# Sheet4_misc.net
KiCad netlist of a schematic drawn in Altium Designer
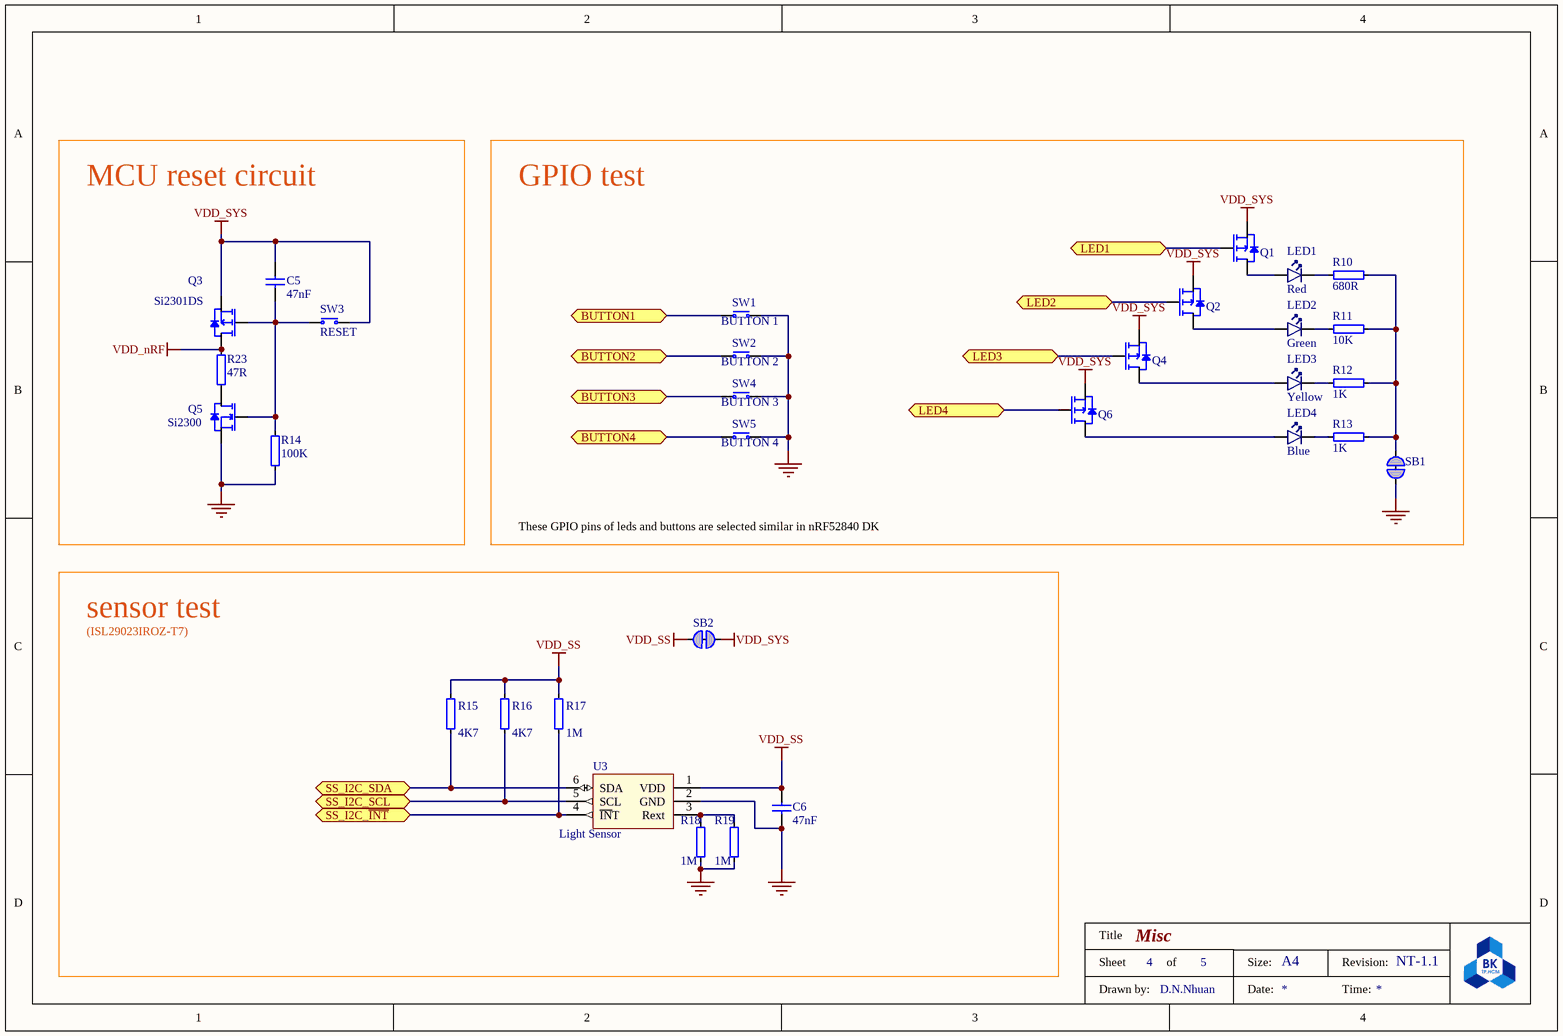
[diagram p0: Sheet4_misc.SchDoc]

(export (version "E")
  (design (tool "Eeschema 10.0.6"))
  (components
    (comp (ref "C5")
      (value "47nF")
      (footprint "0402 imperial")
      (description "Genaral Schematic")
      (fields (field (name "TOLERANCE") "±5%"))
      (libsource (lib "Project_Library") (part "Capacitor"))
    )
    (comp (ref "C6")
      (value "47nF")
      (footprint "0402 imperial")
      (description "Genaral Schematic")
      (fields (field (name "TOLERANCE") "±5%"))
      (libsource (lib "Project_Library") (part "Capacitor"))
    )
    (comp (ref "LED1")
      (value "Red")
      (footprint "LED_0603")
      (description "General Schematic")
      (libsource (lib "Project_library") (part "LED"))
    )
    (comp (ref "LED2")
      (value "Green")
      (footprint "LED_0603")
      (description "General Schematic")
      (libsource (lib "Project_library") (part "LED"))
    )
    (comp (ref "LED3")
      (value "Yellow")
      (footprint "LED_0603")
      (description "General Schematic")
      (libsource (lib "Project_library") (part "LED"))
    )
    (comp (ref "LED4")
      (value "Blue")
      (footprint "LED_0603")
      (description "General Schematic")
      (libsource (lib "Project_library") (part "LED"))
    )
    (comp (ref "Q1")
      (value "Si2301DS")
      (footprint "SOT-23")
      (description "SOT-23 1-G 2-S 3-D")
      (libsource (lib "Project_library") (part "MOS-P"))
    )
    (comp (ref "Q2")
      (value "Si2301DS")
      (footprint "SOT-23")
      (description "SOT-23 1-G 2-S 3-D")
      (libsource (lib "Project_library") (part "MOS-P"))
    )
    (comp (ref "Q3")
      (value "Si2301DS")
      (footprint "SOT-23")
      (description "SOT-23 1-G 2-S 3-D")
      (libsource (lib "Project_Library") (part "MOS-P"))
    )
    (comp (ref "Q4")
      (value "Si2301DS")
      (footprint "SOT-23")
      (description "SOT-23 1-G 2-S 3-D")
      (libsource (lib "Project_library") (part "MOS-P"))
    )
    (comp (ref "Q5")
      (value "Si2300")
      (footprint "SOT-23")
      (description "SOT-23 1-G 2-S 3-D")
      (libsource (lib "Project_Library") (part "MOS-N"))
    )
    (comp (ref "Q6")
      (value "Si2301DS")
      (footprint "SOT-23")
      (description "SOT-23 1-G 2-S 3-D")
      (libsource (lib "Project_library") (part "MOS-P"))
    )
    (comp (ref "R10")
      (value "680R")
      (footprint "0805_Imperial")
      (description "General Schematic")
      (fields (field (name "TOLERANCE") "±5%"))
      (libsource (lib "Project_library") (part "Resistor"))
    )
    (comp (ref "R11")
      (value "10K")
      (footprint "0805_Imperial")
      (description "General Schematic")
      (fields (field (name "TOLERANCE") "±5%"))
      (libsource (lib "Project_library") (part "Resistor"))
    )
    (comp (ref "R12")
      (value "1K")
      (footprint "0805_Imperial")
      (description "General Schematic")
      (fields (field (name "TOLERANCE") "±5%"))
      (libsource (lib "Project_library") (part "Resistor"))
    )
    (comp (ref "R13")
      (value "1K")
      (footprint "0805_Imperial")
      (description "General Schematic")
      (fields (field (name "TOLERANCE") "±5%"))
      (libsource (lib "Project_library") (part "Resistor"))
    )
    (comp (ref "R14")
      (value "100K")
      (footprint "0402 imperial")
      (description "General Schematic")
      (fields (field (name "TOLERANCE") "±5%"))
      (libsource (lib "Project_Library") (part "Resistor"))
    )
    (comp (ref "R15")
      (value "4K7")
      (footprint "0402 imperial")
      (description "General Schematic")
      (fields (field (name "TOLERANCE") "±5%"))
      (libsource (lib "Project_Library") (part "Resistor"))
    )
    (comp (ref "R16")
      (value "4K7")
      (footprint "0402 imperial")
      (description "General Schematic")
      (fields (field (name "TOLERANCE") "±5%"))
      (libsource (lib "Project_Library") (part "Resistor"))
    )
    (comp (ref "R17")
      (value "1M")
      (footprint "0402 imperial")
      (description "General Schematic")
      (fields (field (name "TOLERANCE") "±5%"))
      (libsource (lib "Project_Library") (part "Resistor"))
    )
    (comp (ref "R18")
      (value "1M")
      (footprint "0402 imperial")
      (description "General Schematic")
      (fields (field (name "TOLERANCE") "±1%"))
      (libsource (lib "Project_Library") (part "Resistor"))
    )
    (comp (ref "R19")
      (value "1M")
      (footprint "0402 imperial")
      (description "General Schematic")
      (fields (field (name "TOLERANCE") "±1%"))
      (libsource (lib "Project_Library") (part "Resistor"))
    )
    (comp (ref "R23")
      (value "47R")
      (footprint "0805_Imperial")
      (description "General Schematic")
      (fields (field (name "TOLERANCE") "±5%"))
      (libsource (lib "Project_Library") (part "Resistor"))
    )
    (comp (ref "SB1")
      (value "Solderbridge")
      (footprint "Solderbridge_Shorted")
      (description "Shorted Solderbridge")
      (fields
        (field (name "PART NUMBER") "Solderbridge Shorted")
        (field (name "PUBLISHER") "Nordic Semiconductor")
      )
      (libsource (lib "pca10056") (part "Solderbridge Shorted"))
    )
    (comp (ref "SB2")
      (value "Solderbridge")
      (footprint "Solderbridge_Shorted")
      (description "Shorted Solderbridge")
      (fields
        (field (name "PART NUMBER") "Solderbridge Shorted")
        (field (name "PUBLISHER") "Nordic Semiconductor")
      )
      (libsource (lib "pca10056") (part "Solderbridge Shorted"))
    )
    (comp (ref "SW1")
      (value "BUTTON 1")
      (footprint "Switch-PB-4.5x4.5mm-SMD")
      (description "Push Button")
      (libsource (lib "Project_library") (part "Switch-PB"))
    )
    (comp (ref "SW2")
      (value "BUTTON 2")
      (footprint "Switch-PB-4.5x4.5mm-SMD")
      (description "Push Button")
      (libsource (lib "Project_library") (part "Switch-PB"))
    )
    (comp (ref "SW3")
      (value "RESET")
      (footprint "Switch-PB-4.5x4.5mm-SMD")
      (description "Push Button")
      (libsource (lib "Project_Library") (part "Switch-PB"))
    )
    (comp (ref "SW4")
      (value "BUTTON 3")
      (footprint "Switch-PB-4.5x4.5mm-SMD")
      (description "Push Button")
      (libsource (lib "Project_library") (part "Switch-PB"))
    )
    (comp (ref "SW5")
      (value "BUTTON 4")
      (footprint "Switch-PB-4.5x4.5mm-SMD")
      (description "Push Button")
      (libsource (lib "Project_library") (part "Switch-PB"))
    )
    (comp (ref "U3")
      (value "Light Sensor")
      (footprint "SON65P200X210X80-7N")
      (description "Light Sensor, 2.1x2mm")
      (fields
        (field (name "MANUFACTURER") "Intersil")
        (field (name "MANUFACTURER PARTNUMBER") "ISL29023IROZ-T7")
      )
      (libsource (lib "Project_Library") (part "ISL29023IROZ-T7"))
    )
  )
  (nets
    (net (code "1") (name "/BUTTON1") (class "Default")
      (node (ref "SW1") (pin "2") (pinfunction "COM_2") (pintype "passive"))
    )
    (net (code "2") (name "/BUTTON2") (class "Default")
      (node (ref "SW2") (pin "2") (pinfunction "COM_2") (pintype "passive"))
    )
    (net (code "3") (name "/BUTTON3") (class "Default")
      (node (ref "SW4") (pin "2") (pinfunction "COM_2") (pintype "passive"))
    )
    (net (code "4") (name "/BUTTON4") (class "Default")
      (node (ref "SW5") (pin "2") (pinfunction "COM_2") (pintype "passive"))
    )
    (net (code "5") (name "/LED1") (class "Default")
      (node (ref "Q1") (pin "1") (pinfunction "G_1") (pintype "passive"))
    )
    (net (code "6") (name "/LED2") (class "Default")
      (node (ref "Q2") (pin "1") (pinfunction "G_1") (pintype "passive"))
    )
    (net (code "7") (name "/LED3") (class "Default")
      (node (ref "Q4") (pin "1") (pinfunction "G_1") (pintype "passive"))
    )
    (net (code "8") (name "/LED4") (class "Default")
      (node (ref "Q6") (pin "1") (pinfunction "G_1") (pintype "passive"))
    )
    (net (code "9") (name "/SS_I2C_SCL") (class "Default")
      (node (ref "R16") (pin "1") (pinfunction "1_1") (pintype "passive"))
      (node (ref "U3") (pin "5") (pinfunction "SCL_5") (pintype "output"))
    )
    (net (code "10") (name "/SS_I2C_SDA") (class "Default")
      (node (ref "R15") (pin "1") (pinfunction "1_1") (pintype "passive"))
      (node (ref "U3") (pin "6") (pinfunction "SDA_6") (pintype "bidirectional"))
    )
    (net (code "11") (name "/SS_I2C_~{INT}") (class "Default")
      (node (ref "R17") (pin "1") (pinfunction "1_1") (pintype "passive"))
      (node (ref "U3") (pin "4") (pinfunction "~{IN}T_4") (pintype "output"))
    )
    (net (code "12") (name "GND") (class "Default")
      (node (ref "C6") (pin "1") (pinfunction "1_1") (pintype "passive"))
      (node (ref "Q5") (pin "2") (pinfunction "S_2") (pintype "passive"))
      (node (ref "R14") (pin "1") (pinfunction "1_1") (pintype "passive"))
      (node (ref "R18") (pin "1") (pinfunction "1_1") (pintype "passive"))
      (node (ref "R19") (pin "1") (pinfunction "1_1") (pintype "passive"))
      (node (ref "SB1") (pin "2") (pinfunction "1_2") (pintype "passive"))
      (node (ref "SW1") (pin "1") (pinfunction "N.O_1") (pintype "passive"))
      (node (ref "SW2") (pin "1") (pinfunction "N.O_1") (pintype "passive"))
      (node (ref "SW4") (pin "1") (pinfunction "N.O_1") (pintype "passive"))
      (node (ref "SW5") (pin "1") (pinfunction "N.O_1") (pintype "passive"))
      (node (ref "U3") (pin "2") (pinfunction "GND_2") (pintype "power_in"))
      (node (ref "U3") (pin "7") (pinfunction "GND_7") (pintype "power_in"))
    )
    (net (code "13") (name "Net-(LED1-A)") (class "Default")
      (node (ref "LED1") (pin "2") (pinfunction "A_2") (pintype "passive"))
      (node (ref "Q1") (pin "3") (pinfunction "D_3") (pintype "passive"))
    )
    (net (code "14") (name "Net-(LED1-C)") (class "Default")
      (node (ref "LED1") (pin "1") (pinfunction "C_1") (pintype "passive"))
      (node (ref "R10") (pin "1") (pinfunction "1_1") (pintype "passive"))
    )
    (net (code "15") (name "Net-(LED2-A)") (class "Default")
      (node (ref "LED2") (pin "2") (pinfunction "A_2") (pintype "passive"))
      (node (ref "Q2") (pin "3") (pinfunction "D_3") (pintype "passive"))
    )
    (net (code "16") (name "Net-(LED2-C)") (class "Default")
      (node (ref "LED2") (pin "1") (pinfunction "C_1") (pintype "passive"))
      (node (ref "R11") (pin "1") (pinfunction "1_1") (pintype "passive"))
    )
    (net (code "17") (name "Net-(LED3-A)") (class "Default")
      (node (ref "LED3") (pin "2") (pinfunction "A_2") (pintype "passive"))
      (node (ref "Q4") (pin "3") (pinfunction "D_3") (pintype "passive"))
    )
    (net (code "18") (name "Net-(LED3-C)") (class "Default")
      (node (ref "LED3") (pin "1") (pinfunction "C_1") (pintype "passive"))
      (node (ref "R12") (pin "1") (pinfunction "1_1") (pintype "passive"))
    )
    (net (code "19") (name "Net-(LED4-A)") (class "Default")
      (node (ref "LED4") (pin "2") (pinfunction "A_2") (pintype "passive"))
      (node (ref "Q6") (pin "3") (pinfunction "D_3") (pintype "passive"))
    )
    (net (code "20") (name "Net-(LED4-C)") (class "Default")
      (node (ref "LED4") (pin "1") (pinfunction "C_1") (pintype "passive"))
      (node (ref "R13") (pin "1") (pinfunction "1_1") (pintype "passive"))
    )
    (net (code "21") (name "Net-(Q3-G)") (class "Default")
      (node (ref "C5") (pin "1") (pinfunction "1_1") (pintype "passive"))
      (node (ref "Q3") (pin "1") (pinfunction "G_1") (pintype "passive"))
      (node (ref "Q5") (pin "1") (pinfunction "G_1") (pintype "passive"))
      (node (ref "R14") (pin "2") (pinfunction "2_2") (pintype "passive"))
      (node (ref "SW3") (pin "2") (pinfunction "COM_2") (pintype "passive"))
    )
    (net (code "22") (name "Net-(Q5-D)") (class "Default")
      (node (ref "Q5") (pin "3") (pinfunction "D_3") (pintype "passive"))
      (node (ref "R23") (pin "1") (pinfunction "1_1") (pintype "passive"))
    )
    (net (code "23") (name "Net-(SB1-0)") (class "Default")
      (node (ref "R10") (pin "2") (pinfunction "2_2") (pintype "passive"))
      (node (ref "R11") (pin "2") (pinfunction "2_2") (pintype "passive"))
      (node (ref "R12") (pin "2") (pinfunction "2_2") (pintype "passive"))
      (node (ref "R13") (pin "2") (pinfunction "2_2") (pintype "passive"))
      (node (ref "SB1") (pin "1") (pinfunction "0_1") (pintype "passive"))
    )
    (net (code "24") (name "Net-(U3-Rext)") (class "Default")
      (node (ref "R18") (pin "2") (pinfunction "2_2") (pintype "passive"))
      (node (ref "R19") (pin "2") (pinfunction "2_2") (pintype "passive"))
      (node (ref "U3") (pin "3") (pinfunction "Rext_3") (pintype "passive"))
    )
    (net (code "25") (name "VDD_SS") (class "Default")
      (node (ref "C6") (pin "2") (pinfunction "2_2") (pintype "passive"))
      (node (ref "R15") (pin "2") (pinfunction "2_2") (pintype "passive"))
      (node (ref "R16") (pin "2") (pinfunction "2_2") (pintype "passive"))
      (node (ref "R17") (pin "2") (pinfunction "2_2") (pintype "passive"))
      (node (ref "SB2") (pin "2") (pinfunction "1_2") (pintype "passive"))
      (node (ref "U3") (pin "1") (pinfunction "VDD_1") (pintype "power_in"))
    )
    (net (code "26") (name "VDD_SYS") (class "Default")
      (node (ref "C5") (pin "2") (pinfunction "2_2") (pintype "passive"))
      (node (ref "Q1") (pin "2") (pinfunction "S_2") (pintype "passive"))
      (node (ref "Q2") (pin "2") (pinfunction "S_2") (pintype "passive"))
      (node (ref "Q3") (pin "2") (pinfunction "S_2") (pintype "passive"))
      (node (ref "Q4") (pin "2") (pinfunction "S_2") (pintype "passive"))
      (node (ref "Q6") (pin "2") (pinfunction "S_2") (pintype "passive"))
      (node (ref "SB2") (pin "1") (pinfunction "0_1") (pintype "passive"))
      (node (ref "SW3") (pin "1") (pinfunction "N.O_1") (pintype "passive"))
    )
    (net (code "27") (name "VDD_nRF") (class "Default")
      (node (ref "Q3") (pin "3") (pinfunction "D_3") (pintype "passive"))
      (node (ref "R23") (pin "2") (pinfunction "2_2") (pintype "passive"))
    )
  )
)
